# teensyShield4.net
KiCad netlist of a schematic drawn in EAGLE
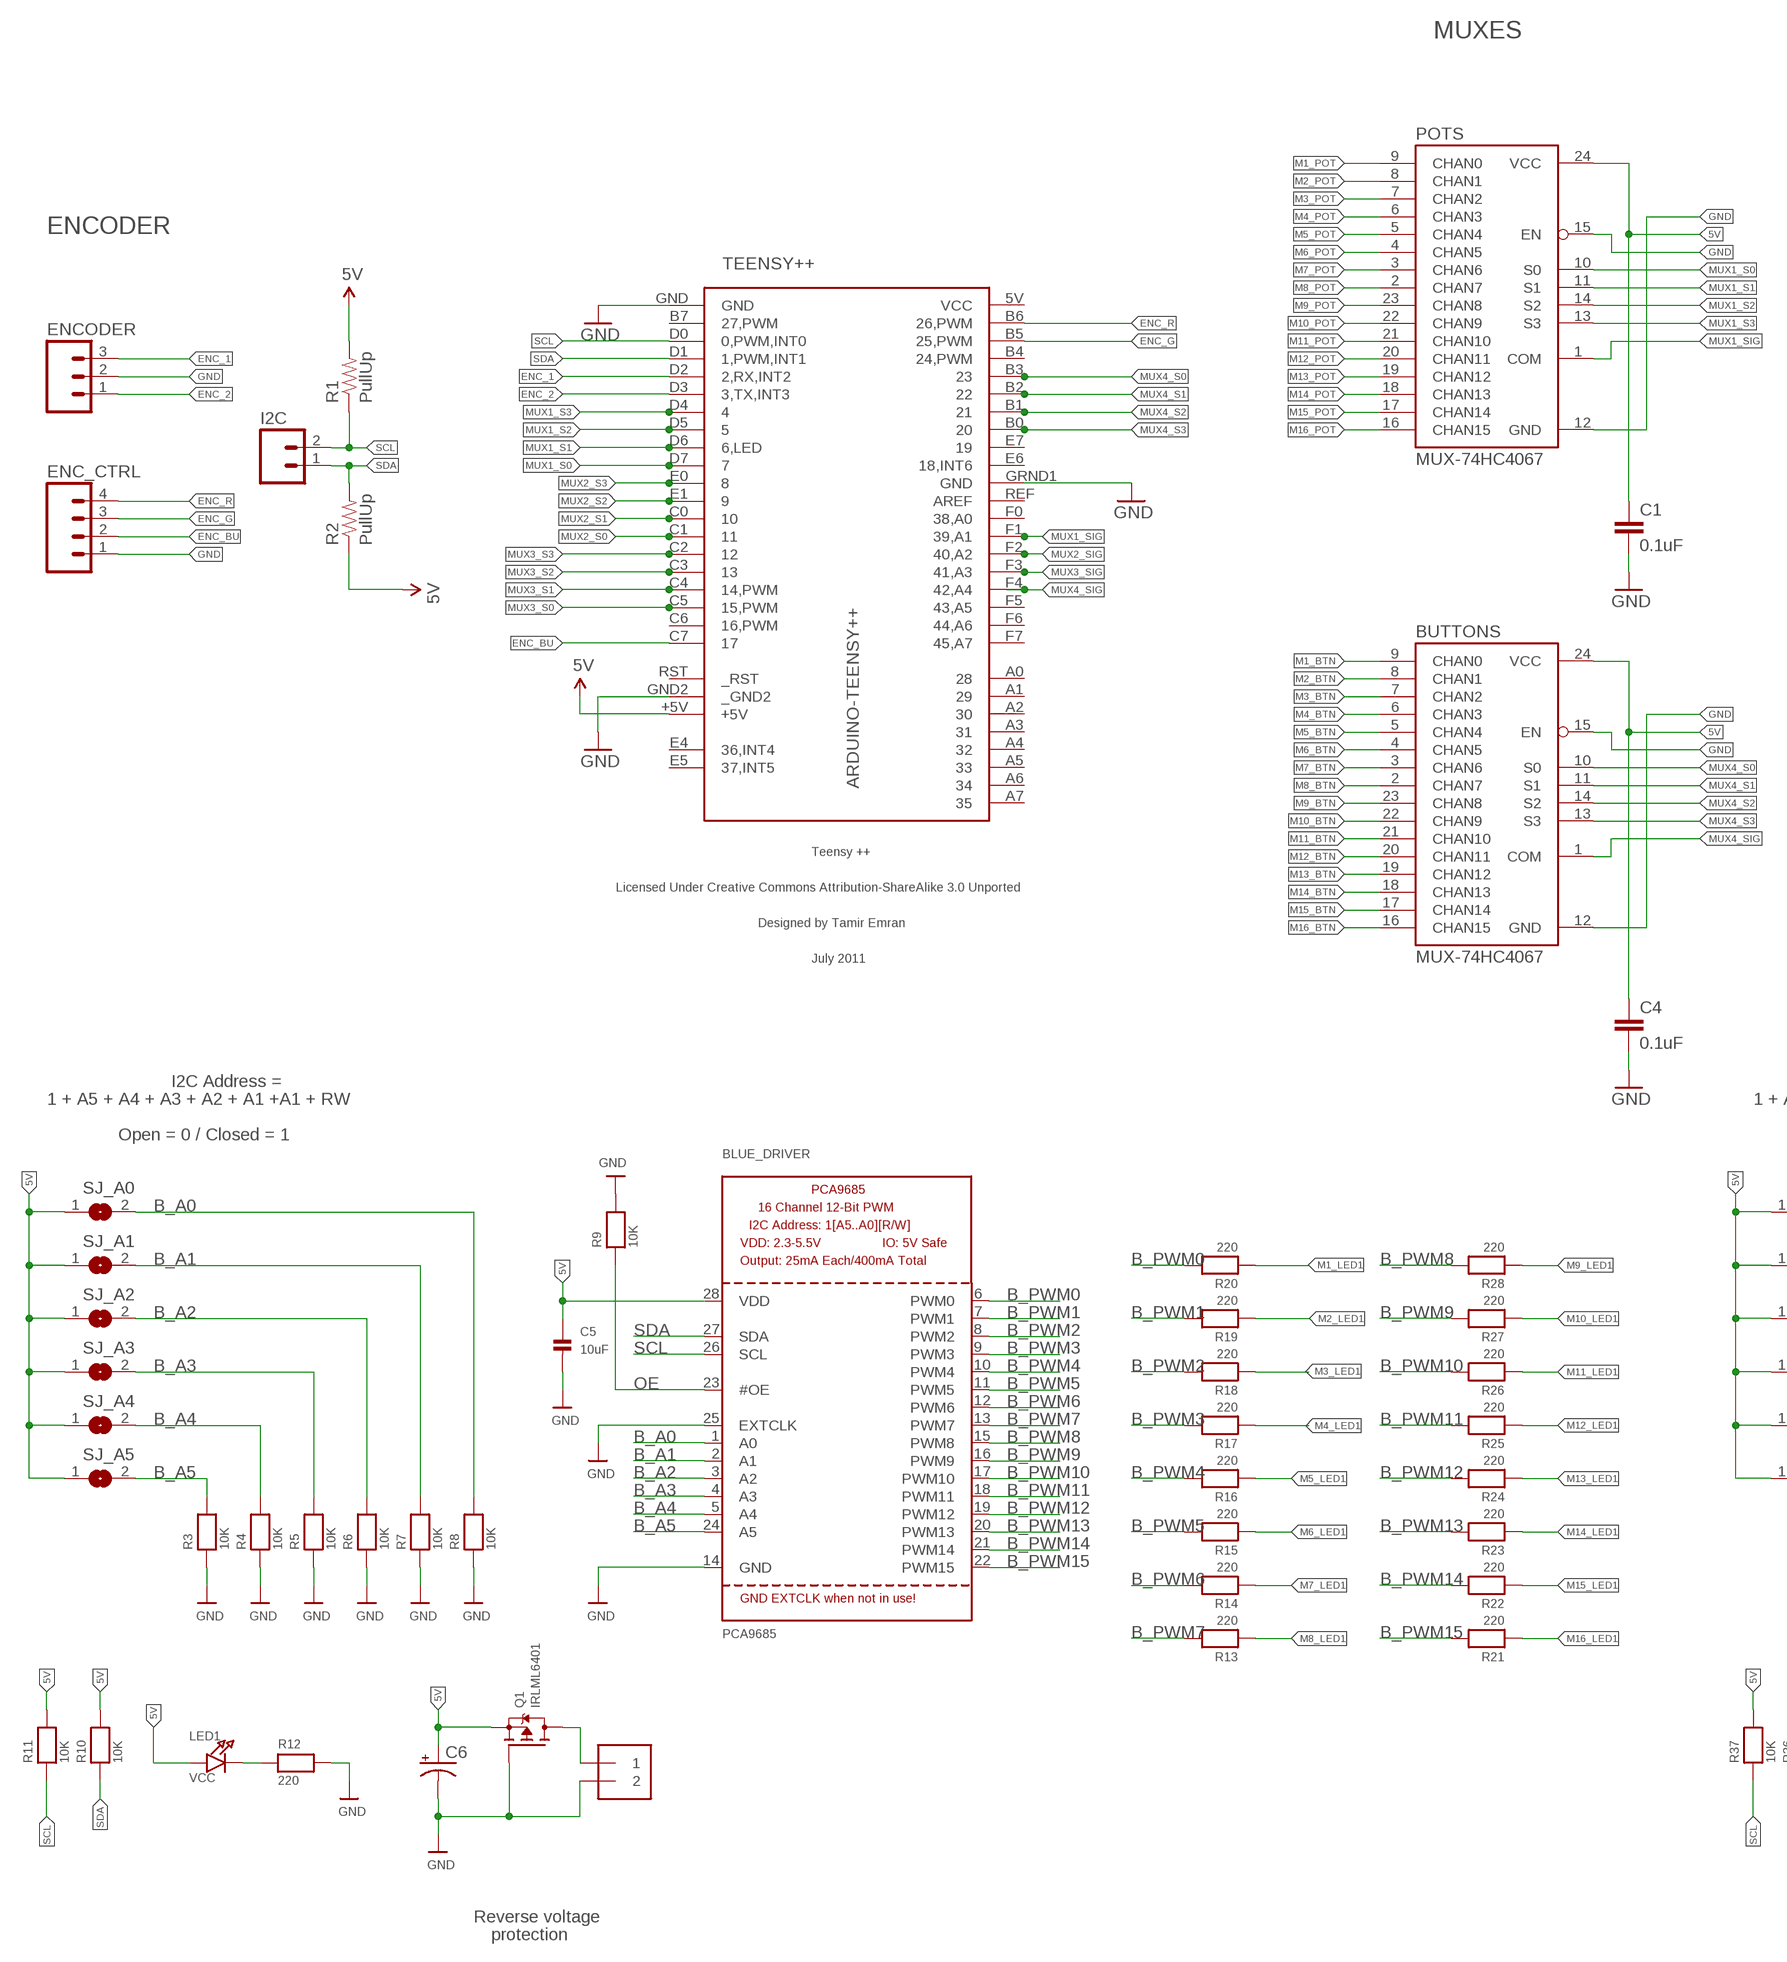
[diagram p0: schematic, sheet 1, part 1 of 2]
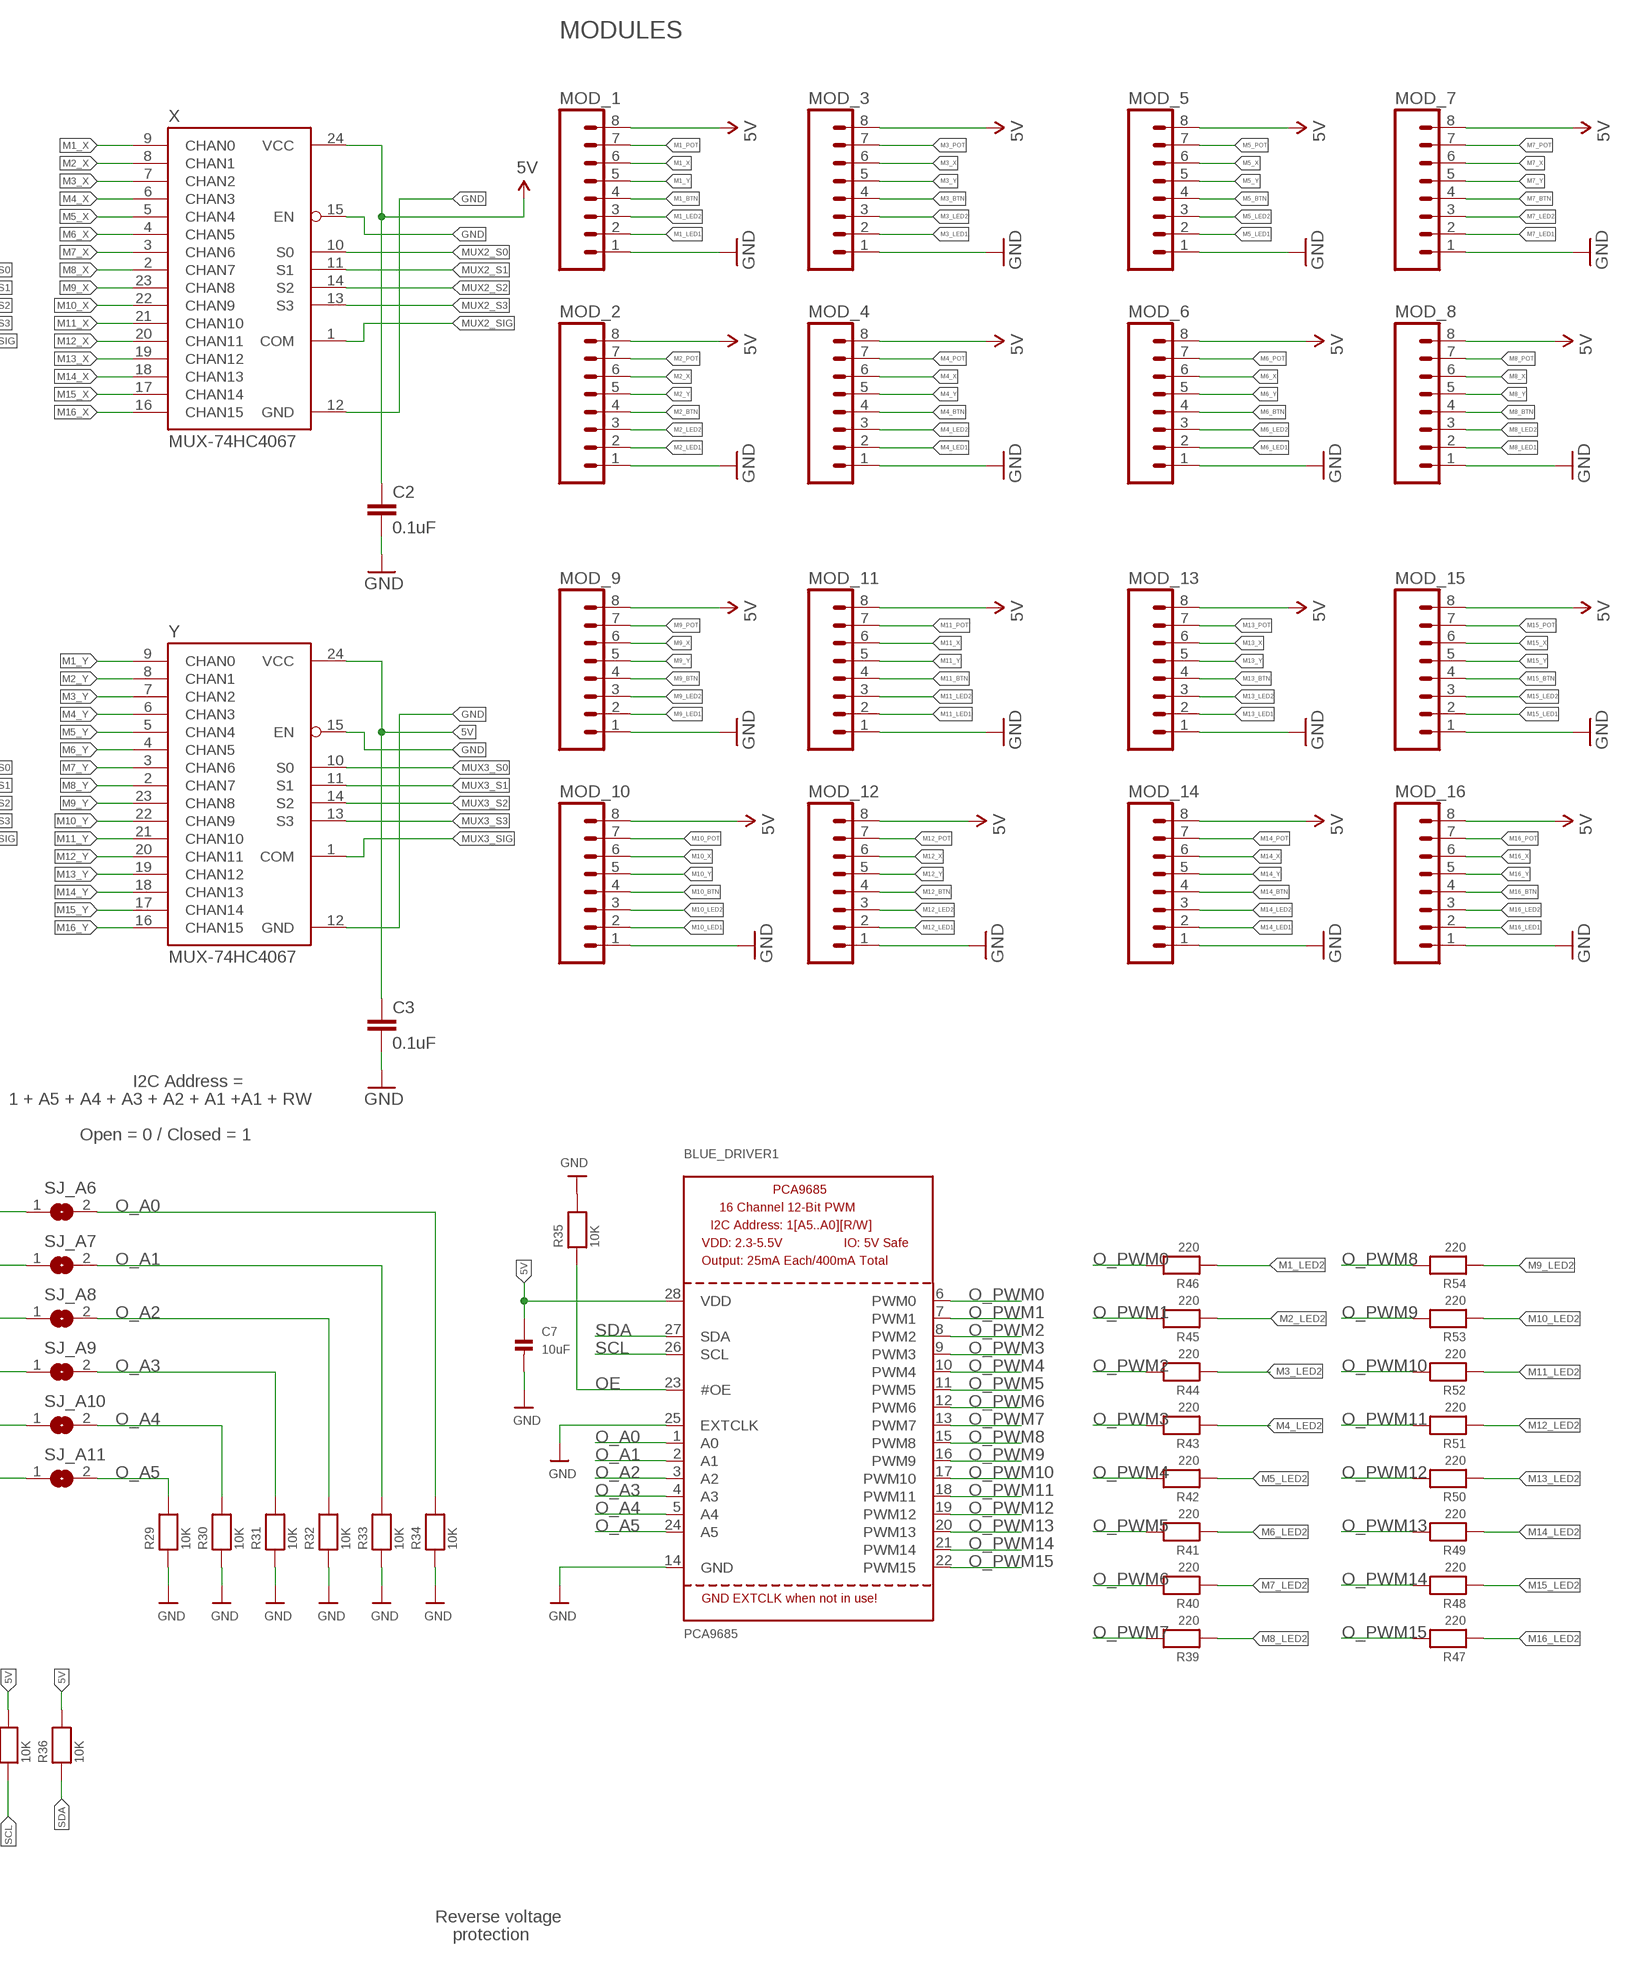
[diagram p1: schematic, sheet 1, part 2 of 2]

(export (version "E")
  (design (tool "Eeschema 10.0.6"))
  (components
    (comp (ref "BLUE_DRIVER")
      (value "PCA9685")
      (footprint "eagle-import:TSSOP28")
      (libsource (lib "eagle-import") (part "PCA9685"))
    )
    (comp (ref "BLUE_DRIVER1")
      (value "PCA9685")
      (footprint "eagle-import:TSSOP28")
      (libsource (lib "eagle-import") (part "PCA9685"))
    )
    (comp (ref "BUTTONS")
      (value "MUX-74HC4067")
      (footprint "eagle-import:SSOP24")
      (libsource (lib "eagle-import") (part "MUX-74HC4067SMD"))
    )
    (comp (ref "C1")
      (value "0.1uF")
      (footprint "eagle-import:0603")
      (libsource (lib "eagle-import") (part "CAP0603"))
    )
    (comp (ref "C2")
      (value "0.1uF")
      (footprint "eagle-import:0603")
      (libsource (lib "eagle-import") (part "CAP0603"))
    )
    (comp (ref "C3")
      (value "0.1uF")
      (footprint "eagle-import:0603")
      (libsource (lib "eagle-import") (part "CAP0603"))
    )
    (comp (ref "C4")
      (value "0.1uF")
      (footprint "eagle-import:0603")
      (libsource (lib "eagle-import") (part "CAP0603"))
    )
    (comp (ref "C5")
      (value "10uF")
      (footprint "eagle-import:0805")
      (libsource (lib "eagle-import") (part "CAP_CERAMIC0805"))
    )
    (comp (ref "C6")
      (value "CPOL-USE3.5-8")
      (footprint "eagle-import:E3,5-8")
      (libsource (lib "eagle-import") (part "CPOL-USE3.5-8"))
    )
    (comp (ref "C7")
      (value "10uF")
      (footprint "eagle-import:0805")
      (libsource (lib "eagle-import") (part "CAP_CERAMIC0805"))
    )
    (comp (ref "ENCODER")
      (value "M031X03_NO_SILK")
      (footprint "eagle-import:1X03_NO_SILK")
      (libsource (lib "eagle-import") (part "M031X03_NO_SILK"))
    )
    (comp (ref "ENC_CTRL")
      (value "M041X04_NO_SILK")
      (footprint "eagle-import:1X04_NO_SILK")
      (libsource (lib "eagle-import") (part "M041X04_NO_SILK"))
    )
    (comp (ref "I2C")
      (value "M02LOCK")
      (footprint "eagle-import:1X02_LOCK")
      (libsource (lib "eagle-import") (part "M02LOCK"))
    )
    (comp (ref "J1")
      (value "TERMBLOCK_1X2-3.5MM")
      (footprint "eagle-import:1X2-3.5MM")
      (libsource (lib "eagle-import") (part "TERMBLOCK_1X2-3.5MM"))
    )
    (comp (ref "LED1")
      (value "VCC")
      (footprint "eagle-import:CHIPLED_0805")
      (libsource (lib "eagle-import") (part "LED0805"))
    )
    (comp (ref "MOD_1")
      (value "M08")
      (footprint "eagle-import:1X08_ROUND")
      (libsource (lib "eagle-import") (part "M08"))
    )
    (comp (ref "MOD_2")
      (value "M08")
      (footprint "eagle-import:1X08_ROUND")
      (libsource (lib "eagle-import") (part "M08"))
    )
    (comp (ref "MOD_3")
      (value "M08")
      (footprint "eagle-import:1X08_ROUND")
      (libsource (lib "eagle-import") (part "M08"))
    )
    (comp (ref "MOD_4")
      (value "M08")
      (footprint "eagle-import:1X08_ROUND")
      (libsource (lib "eagle-import") (part "M08"))
    )
    (comp (ref "MOD_5")
      (value "M08")
      (footprint "eagle-import:1X08_ROUND")
      (libsource (lib "eagle-import") (part "M08"))
    )
    (comp (ref "MOD_6")
      (value "M08")
      (footprint "eagle-import:1X08_ROUND")
      (libsource (lib "eagle-import") (part "M08"))
    )
    (comp (ref "MOD_7")
      (value "M08")
      (footprint "eagle-import:1X08_ROUND")
      (libsource (lib "eagle-import") (part "M08"))
    )
    (comp (ref "MOD_8")
      (value "M08")
      (footprint "eagle-import:1X08_ROUND")
      (libsource (lib "eagle-import") (part "M08"))
    )
    (comp (ref "MOD_9")
      (value "M08")
      (footprint "eagle-import:1X08_ROUND")
      (libsource (lib "eagle-import") (part "M08"))
    )
    (comp (ref "MOD_10")
      (value "M08")
      (footprint "eagle-import:1X08_ROUND")
      (libsource (lib "eagle-import") (part "M08"))
    )
    (comp (ref "MOD_11")
      (value "M08")
      (footprint "eagle-import:1X08_ROUND")
      (libsource (lib "eagle-import") (part "M08"))
    )
    (comp (ref "MOD_12")
      (value "M08")
      (footprint "eagle-import:1X08_ROUND")
      (libsource (lib "eagle-import") (part "M08"))
    )
    (comp (ref "MOD_13")
      (value "M08")
      (footprint "eagle-import:1X08_ROUND")
      (libsource (lib "eagle-import") (part "M08"))
    )
    (comp (ref "MOD_14")
      (value "M08")
      (footprint "eagle-import:1X08_ROUND")
      (libsource (lib "eagle-import") (part "M08"))
    )
    (comp (ref "MOD_15")
      (value "M08")
      (footprint "eagle-import:1X08_ROUND")
      (libsource (lib "eagle-import") (part "M08"))
    )
    (comp (ref "MOD_16")
      (value "M08")
      (footprint "eagle-import:1X08_ROUND")
      (libsource (lib "eagle-import") (part "M08"))
    )
    (comp (ref "POTS")
      (value "MUX-74HC4067")
      (footprint "eagle-import:SSOP24")
      (libsource (lib "eagle-import") (part "MUX-74HC4067SMD"))
    )
    (comp (ref "Q1")
      (value "IRLML6401")
      (footprint "eagle-import:SOT23-WIDE")
      (libsource (lib "eagle-import") (part "MOSFET-PWIDE"))
    )
    (comp (ref "R1")
      (value "PullUp")
      (footprint "eagle-import:AXIAL-0.3")
      (libsource (lib "eagle-import") (part "10KOHM-1/4W5%(PTH)"))
    )
    (comp (ref "R2")
      (value "PullUp")
      (footprint "eagle-import:AXIAL-0.3")
      (libsource (lib "eagle-import") (part "10KOHM-1/4W5%(PTH)"))
    )
    (comp (ref "R3")
      (value "10K")
      (footprint "eagle-import:0805")
      (libsource (lib "eagle-import") (part "RESISTOR0805"))
    )
    (comp (ref "R4")
      (value "10K")
      (footprint "eagle-import:0805")
      (libsource (lib "eagle-import") (part "RESISTOR0805"))
    )
    (comp (ref "R5")
      (value "10K")
      (footprint "eagle-import:0805")
      (libsource (lib "eagle-import") (part "RESISTOR0805"))
    )
    (comp (ref "R6")
      (value "10K")
      (footprint "eagle-import:0805")
      (libsource (lib "eagle-import") (part "RESISTOR0805"))
    )
    (comp (ref "R7")
      (value "10K")
      (footprint "eagle-import:0805")
      (libsource (lib "eagle-import") (part "RESISTOR0805"))
    )
    (comp (ref "R8")
      (value "10K")
      (footprint "eagle-import:0805")
      (libsource (lib "eagle-import") (part "RESISTOR0805"))
    )
    (comp (ref "R9")
      (value "10K")
      (footprint "eagle-import:0805")
      (libsource (lib "eagle-import") (part "RESISTOR0805"))
    )
    (comp (ref "R10")
      (value "10K")
      (footprint "eagle-import:0805")
      (libsource (lib "eagle-import") (part "RESISTOR0805"))
    )
    (comp (ref "R11")
      (value "10K")
      (footprint "eagle-import:0805")
      (libsource (lib "eagle-import") (part "RESISTOR0805"))
    )
    (comp (ref "R12")
      (value "220")
      (footprint "eagle-import:0805")
      (libsource (lib "eagle-import") (part "RESISTOR0805"))
    )
    (comp (ref "R13")
      (value "220")
      (footprint "eagle-import:0805")
      (libsource (lib "eagle-import") (part "RESISTOR0805"))
    )
    (comp (ref "R14")
      (value "220")
      (footprint "eagle-import:0805")
      (libsource (lib "eagle-import") (part "RESISTOR0805"))
    )
    (comp (ref "R15")
      (value "220")
      (footprint "eagle-import:0805")
      (libsource (lib "eagle-import") (part "RESISTOR0805"))
    )
    (comp (ref "R16")
      (value "220")
      (footprint "eagle-import:0805")
      (libsource (lib "eagle-import") (part "RESISTOR0805"))
    )
    (comp (ref "R17")
      (value "220")
      (footprint "eagle-import:0805")
      (libsource (lib "eagle-import") (part "RESISTOR0805"))
    )
    (comp (ref "R18")
      (value "220")
      (footprint "eagle-import:0805")
      (libsource (lib "eagle-import") (part "RESISTOR0805"))
    )
    (comp (ref "R19")
      (value "220")
      (footprint "eagle-import:0805")
      (libsource (lib "eagle-import") (part "RESISTOR0805"))
    )
    (comp (ref "R20")
      (value "220")
      (footprint "eagle-import:0805")
      (libsource (lib "eagle-import") (part "RESISTOR0805"))
    )
    (comp (ref "R21")
      (value "220")
      (footprint "eagle-import:0805")
      (libsource (lib "eagle-import") (part "RESISTOR0805"))
    )
    (comp (ref "R22")
      (value "220")
      (footprint "eagle-import:0805")
      (libsource (lib "eagle-import") (part "RESISTOR0805"))
    )
    (comp (ref "R23")
      (value "220")
      (footprint "eagle-import:0805")
      (libsource (lib "eagle-import") (part "RESISTOR0805"))
    )
    (comp (ref "R24")
      (value "220")
      (footprint "eagle-import:0805")
      (libsource (lib "eagle-import") (part "RESISTOR0805"))
    )
    (comp (ref "R25")
      (value "220")
      (footprint "eagle-import:0805")
      (libsource (lib "eagle-import") (part "RESISTOR0805"))
    )
    (comp (ref "R26")
      (value "220")
      (footprint "eagle-import:0805")
      (libsource (lib "eagle-import") (part "RESISTOR0805"))
    )
    (comp (ref "R27")
      (value "220")
      (footprint "eagle-import:0805")
      (libsource (lib "eagle-import") (part "RESISTOR0805"))
    )
    (comp (ref "R28")
      (value "220")
      (footprint "eagle-import:0805")
      (libsource (lib "eagle-import") (part "RESISTOR0805"))
    )
    (comp (ref "R29")
      (value "10K")
      (footprint "eagle-import:0805")
      (libsource (lib "eagle-import") (part "RESISTOR0805"))
    )
    (comp (ref "R30")
      (value "10K")
      (footprint "eagle-import:0805")
      (libsource (lib "eagle-import") (part "RESISTOR0805"))
    )
    (comp (ref "R31")
      (value "10K")
      (footprint "eagle-import:0805")
      (libsource (lib "eagle-import") (part "RESISTOR0805"))
    )
    (comp (ref "R32")
      (value "10K")
      (footprint "eagle-import:0805")
      (libsource (lib "eagle-import") (part "RESISTOR0805"))
    )
    (comp (ref "R33")
      (value "10K")
      (footprint "eagle-import:0805")
      (libsource (lib "eagle-import") (part "RESISTOR0805"))
    )
    (comp (ref "R34")
      (value "10K")
      (footprint "eagle-import:0805")
      (libsource (lib "eagle-import") (part "RESISTOR0805"))
    )
    (comp (ref "R35")
      (value "10K")
      (footprint "eagle-import:0805")
      (libsource (lib "eagle-import") (part "RESISTOR0805"))
    )
    (comp (ref "R36")
      (value "10K")
      (footprint "eagle-import:0805")
      (libsource (lib "eagle-import") (part "RESISTOR0805"))
    )
    (comp (ref "R37")
      (value "10K")
      (footprint "eagle-import:0805")
      (libsource (lib "eagle-import") (part "RESISTOR0805"))
    )
    (comp (ref "R39")
      (value "220")
      (footprint "eagle-import:0805")
      (libsource (lib "eagle-import") (part "RESISTOR0805"))
    )
    (comp (ref "R40")
      (value "220")
      (footprint "eagle-import:0805")
      (libsource (lib "eagle-import") (part "RESISTOR0805"))
    )
    (comp (ref "R41")
      (value "220")
      (footprint "eagle-import:0805")
      (libsource (lib "eagle-import") (part "RESISTOR0805"))
    )
    (comp (ref "R42")
      (value "220")
      (footprint "eagle-import:0805")
      (libsource (lib "eagle-import") (part "RESISTOR0805"))
    )
    (comp (ref "R43")
      (value "220")
      (footprint "eagle-import:0805")
      (libsource (lib "eagle-import") (part "RESISTOR0805"))
    )
    (comp (ref "R44")
      (value "220")
      (footprint "eagle-import:0805")
      (libsource (lib "eagle-import") (part "RESISTOR0805"))
    )
    (comp (ref "R45")
      (value "220")
      (footprint "eagle-import:0805")
      (libsource (lib "eagle-import") (part "RESISTOR0805"))
    )
    (comp (ref "R46")
      (value "220")
      (footprint "eagle-import:0805")
      (libsource (lib "eagle-import") (part "RESISTOR0805"))
    )
    (comp (ref "R47")
      (value "220")
      (footprint "eagle-import:0805")
      (libsource (lib "eagle-import") (part "RESISTOR0805"))
    )
    (comp (ref "R48")
      (value "220")
      (footprint "eagle-import:0805")
      (libsource (lib "eagle-import") (part "RESISTOR0805"))
    )
    (comp (ref "R49")
      (value "220")
      (footprint "eagle-import:0805")
      (libsource (lib "eagle-import") (part "RESISTOR0805"))
    )
    (comp (ref "R50")
      (value "220")
      (footprint "eagle-import:0805")
      (libsource (lib "eagle-import") (part "RESISTOR0805"))
    )
    (comp (ref "R51")
      (value "220")
      (footprint "eagle-import:0805")
      (libsource (lib "eagle-import") (part "RESISTOR0805"))
    )
    (comp (ref "R52")
      (value "220")
      (footprint "eagle-import:0805")
      (libsource (lib "eagle-import") (part "RESISTOR0805"))
    )
    (comp (ref "R53")
      (value "220")
      (footprint "eagle-import:0805")
      (libsource (lib "eagle-import") (part "RESISTOR0805"))
    )
    (comp (ref "R54")
      (value "220")
      (footprint "eagle-import:0805")
      (libsource (lib "eagle-import") (part "RESISTOR0805"))
    )
    (comp (ref "SJ_A0")
      (value "SOLDERJUMPERREFLOW_NOPASTE")
      (footprint "eagle-import:SOLDERJUMPER_REFLOW_NOPASTE")
      (libsource (lib "eagle-import") (part "SOLDERJUMPERREFLOW_NOPASTE"))
    )
    (comp (ref "SJ_A1")
      (value "SOLDERJUMPERREFLOW_NOPASTE")
      (footprint "eagle-import:SOLDERJUMPER_REFLOW_NOPASTE")
      (libsource (lib "eagle-import") (part "SOLDERJUMPERREFLOW_NOPASTE"))
    )
    (comp (ref "SJ_A2")
      (value "SOLDERJUMPERREFLOW_NOPASTE")
      (footprint "eagle-import:SOLDERJUMPER_REFLOW_NOPASTE")
      (libsource (lib "eagle-import") (part "SOLDERJUMPERREFLOW_NOPASTE"))
    )
    (comp (ref "SJ_A3")
      (value "SOLDERJUMPERREFLOW_NOPASTE")
      (footprint "eagle-import:SOLDERJUMPER_REFLOW_NOPASTE")
      (libsource (lib "eagle-import") (part "SOLDERJUMPERREFLOW_NOPASTE"))
    )
    (comp (ref "SJ_A4")
      (value "SOLDERJUMPERREFLOW_NOPASTE")
      (footprint "eagle-import:SOLDERJUMPER_REFLOW_NOPASTE")
      (libsource (lib "eagle-import") (part "SOLDERJUMPERREFLOW_NOPASTE"))
    )
    (comp (ref "SJ_A5")
      (value "SOLDERJUMPERREFLOW_NOPASTE")
      (footprint "eagle-import:SOLDERJUMPER_REFLOW_NOPASTE")
      (libsource (lib "eagle-import") (part "SOLDERJUMPERREFLOW_NOPASTE"))
    )
    (comp (ref "SJ_A6")
      (value "SOLDERJUMPERREFLOW_NOPASTE")
      (footprint "eagle-import:SOLDERJUMPER_REFLOW_NOPASTE")
      (libsource (lib "eagle-import") (part "SOLDERJUMPERREFLOW_NOPASTE"))
    )
    (comp (ref "SJ_A7")
      (value "SOLDERJUMPERREFLOW_NOPASTE")
      (footprint "eagle-import:SOLDERJUMPER_REFLOW_NOPASTE")
      (libsource (lib "eagle-import") (part "SOLDERJUMPERREFLOW_NOPASTE"))
    )
    (comp (ref "SJ_A8")
      (value "SOLDERJUMPERREFLOW_NOPASTE")
      (footprint "eagle-import:SOLDERJUMPER_REFLOW_NOPASTE")
      (libsource (lib "eagle-import") (part "SOLDERJUMPERREFLOW_NOPASTE"))
    )
    (comp (ref "SJ_A9")
      (value "SOLDERJUMPERREFLOW_NOPASTE")
      (footprint "eagle-import:SOLDERJUMPER_REFLOW_NOPASTE")
      (libsource (lib "eagle-import") (part "SOLDERJUMPERREFLOW_NOPASTE"))
    )
    (comp (ref "SJ_A10")
      (value "SOLDERJUMPERREFLOW_NOPASTE")
      (footprint "eagle-import:SOLDERJUMPER_REFLOW_NOPASTE")
      (libsource (lib "eagle-import") (part "SOLDERJUMPERREFLOW_NOPASTE"))
    )
    (comp (ref "SJ_A11")
      (value "SOLDERJUMPERREFLOW_NOPASTE")
      (footprint "eagle-import:SOLDERJUMPER_REFLOW_NOPASTE")
      (libsource (lib "eagle-import") (part "SOLDERJUMPERREFLOW_NOPASTE"))
    )
    (comp (ref "TEENSY++")
      (value "ARDUINO-TEENSY++")
      (footprint "eagle-import:TEENSY++")
      (libsource (lib "eagle-import") (part "ARDUINO-TEENSY++"))
    )
    (comp (ref "X")
      (value "MUX-74HC4067")
      (footprint "eagle-import:SSOP24")
      (libsource (lib "eagle-import") (part "MUX-74HC4067SMD"))
    )
    (comp (ref "Y")
      (value "MUX-74HC4067")
      (footprint "eagle-import:SSOP24")
      (libsource (lib "eagle-import") (part "MUX-74HC4067SMD"))
    )
  )
  (nets
    (net (code "1") (name "/B_A0") (class "Default")
      (node (ref "BLUE_DRIVER") (pin "1") (pinfunction "A0_1") (pintype "bidirectional"))
      (node (ref "R8") (pin "2") (pinfunction "2_2") (pintype "passive"))
      (node (ref "SJ_A0") (pin "2") (pinfunction "2_2") (pintype "passive"))
    )
    (net (code "2") (name "/B_A1") (class "Default")
      (node (ref "BLUE_DRIVER") (pin "2") (pinfunction "A1_2") (pintype "bidirectional"))
      (node (ref "R7") (pin "2") (pinfunction "2_2") (pintype "passive"))
      (node (ref "SJ_A1") (pin "2") (pinfunction "2_2") (pintype "passive"))
    )
    (net (code "3") (name "/B_A2") (class "Default")
      (node (ref "BLUE_DRIVER") (pin "3") (pinfunction "A2_3") (pintype "bidirectional"))
      (node (ref "R6") (pin "2") (pinfunction "2_2") (pintype "passive"))
      (node (ref "SJ_A2") (pin "2") (pinfunction "2_2") (pintype "passive"))
    )
    (net (code "4") (name "/B_A3") (class "Default")
      (node (ref "BLUE_DRIVER") (pin "4") (pinfunction "A3_4") (pintype "bidirectional"))
      (node (ref "R5") (pin "2") (pinfunction "2_2") (pintype "passive"))
      (node (ref "SJ_A3") (pin "2") (pinfunction "2_2") (pintype "passive"))
    )
    (net (code "5") (name "/B_A4") (class "Default")
      (node (ref "BLUE_DRIVER") (pin "5") (pinfunction "A4_5") (pintype "bidirectional"))
      (node (ref "R4") (pin "2") (pinfunction "2_2") (pintype "passive"))
      (node (ref "SJ_A4") (pin "2") (pinfunction "2_2") (pintype "passive"))
    )
    (net (code "6") (name "/B_A5") (class "Default")
      (node (ref "BLUE_DRIVER") (pin "24") (pinfunction "A5_24") (pintype "bidirectional"))
      (node (ref "R3") (pin "2") (pinfunction "2_2") (pintype "passive"))
      (node (ref "SJ_A5") (pin "2") (pinfunction "2_2") (pintype "passive"))
    )
    (net (code "7") (name "/B_PWM0") (class "Default")
      (node (ref "BLUE_DRIVER") (pin "6") (pinfunction "PWM0_6") (pintype "output"))
      (node (ref "R20") (pin "2") (pinfunction "2_2") (pintype "passive"))
    )
    (net (code "8") (name "/B_PWM1") (class "Default")
      (node (ref "BLUE_DRIVER") (pin "7") (pinfunction "PWM1_7") (pintype "output"))
      (node (ref "R19") (pin "2") (pinfunction "2_2") (pintype "passive"))
    )
    (net (code "9") (name "/B_PWM2") (class "Default")
      (node (ref "BLUE_DRIVER") (pin "8") (pinfunction "PWM2_8") (pintype "output"))
      (node (ref "R18") (pin "2") (pinfunction "2_2") (pintype "passive"))
    )
    (net (code "10") (name "/B_PWM3") (class "Default")
      (node (ref "BLUE_DRIVER") (pin "9") (pinfunction "PWM3_9") (pintype "output"))
      (node (ref "R17") (pin "2") (pinfunction "2_2") (pintype "passive"))
    )
    (net (code "11") (name "/B_PWM4") (class "Default")
      (node (ref "BLUE_DRIVER") (pin "10") (pinfunction "PWM4_10") (pintype "output"))
      (node (ref "R16") (pin "2") (pinfunction "2_2") (pintype "passive"))
    )
    (net (code "12") (name "/B_PWM5") (class "Default")
      (node (ref "BLUE_DRIVER") (pin "11") (pinfunction "PWM5_11") (pintype "output"))
      (node (ref "R15") (pin "2") (pinfunction "2_2") (pintype "passive"))
    )
    (net (code "13") (name "/B_PWM6") (class "Default")
      (node (ref "BLUE_DRIVER") (pin "12") (pinfunction "PWM6_12") (pintype "output"))
      (node (ref "R14") (pin "2") (pinfunction "2_2") (pintype "passive"))
    )
    (net (code "14") (name "/B_PWM7") (class "Default")
      (node (ref "BLUE_DRIVER") (pin "13") (pinfunction "PWM7_13") (pintype "output"))
      (node (ref "R13") (pin "2") (pinfunction "2_2") (pintype "passive"))
    )
    (net (code "15") (name "/B_PWM8") (class "Default")
      (node (ref "BLUE_DRIVER") (pin "15") (pinfunction "PWM8_15") (pintype "output"))
      (node (ref "R28") (pin "2") (pinfunction "2_2") (pintype "passive"))
    )
    (net (code "16") (name "/B_PWM9") (class "Default")
      (node (ref "BLUE_DRIVER") (pin "16") (pinfunction "PWM9_16") (pintype "output"))
      (node (ref "R27") (pin "2") (pinfunction "2_2") (pintype "passive"))
    )
    (net (code "17") (name "/B_PWM10") (class "Default")
      (node (ref "BLUE_DRIVER") (pin "17") (pinfunction "PWM10_17") (pintype "output"))
      (node (ref "R26") (pin "2") (pinfunction "2_2") (pintype "passive"))
    )
    (net (code "18") (name "/B_PWM11") (class "Default")
      (node (ref "BLUE_DRIVER") (pin "18") (pinfunction "PWM11_18") (pintype "output"))
      (node (ref "R25") (pin "2") (pinfunction "2_2") (pintype "passive"))
    )
    (net (code "19") (name "/B_PWM12") (class "Default")
      (node (ref "BLUE_DRIVER") (pin "19") (pinfunction "PWM12_19") (pintype "output"))
      (node (ref "R24") (pin "2") (pinfunction "2_2") (pintype "passive"))
    )
    (net (code "20") (name "/B_PWM13") (class "Default")
      (node (ref "BLUE_DRIVER") (pin "20") (pinfunction "PWM13_20") (pintype "output"))
      (node (ref "R23") (pin "2") (pinfunction "2_2") (pintype "passive"))
    )
    (net (code "21") (name "/B_PWM14") (class "Default")
      (node (ref "BLUE_DRIVER") (pin "21") (pinfunction "PWM14_21") (pintype "output"))
      (node (ref "R22") (pin "2") (pinfunction "2_2") (pintype "passive"))
    )
    (net (code "22") (name "/B_PWM15") (class "Default")
      (node (ref "BLUE_DRIVER") (pin "22") (pinfunction "PWM15_22") (pintype "output"))
      (node (ref "R21") (pin "2") (pinfunction "2_2") (pintype "passive"))
    )
    (net (code "23") (name "/OE") (class "Default")
      (node (ref "BLUE_DRIVER") (pin "23") (pinfunction "#OE_23") (pintype "input"))
      (node (ref "BLUE_DRIVER1") (pin "23") (pinfunction "#OE_23") (pintype "input"))
      (node (ref "R35") (pin "1") (pinfunction "1_1") (pintype "passive"))
      (node (ref "R9") (pin "1") (pinfunction "1_1") (pintype "passive"))
    )
    (net (code "24") (name "/O_A0") (class "Default")
      (node (ref "BLUE_DRIVER1") (pin "1") (pinfunction "A0_1") (pintype "bidirectional"))
      (node (ref "R34") (pin "2") (pinfunction "2_2") (pintype "passive"))
      (node (ref "SJ_A6") (pin "2") (pinfunction "2_2") (pintype "passive"))
    )
    (net (code "25") (name "/O_A1") (class "Default")
      (node (ref "BLUE_DRIVER1") (pin "2") (pinfunction "A1_2") (pintype "bidirectional"))
      (node (ref "R33") (pin "2") (pinfunction "2_2") (pintype "passive"))
      (node (ref "SJ_A7") (pin "2") (pinfunction "2_2") (pintype "passive"))
    )
    (net (code "26") (name "/O_A2") (class "Default")
      (node (ref "BLUE_DRIVER1") (pin "3") (pinfunction "A2_3") (pintype "bidirectional"))
      (node (ref "R32") (pin "2") (pinfunction "2_2") (pintype "passive"))
      (node (ref "SJ_A8") (pin "2") (pinfunction "2_2") (pintype "passive"))
    )
    (net (code "27") (name "/O_A3") (class "Default")
      (node (ref "BLUE_DRIVER1") (pin "4") (pinfunction "A3_4") (pintype "bidirectional"))
      (node (ref "R31") (pin "2") (pinfunction "2_2") (pintype "passive"))
      (node (ref "SJ_A9") (pin "2") (pinfunction "2_2") (pintype "passive"))
    )
    (net (code "28") (name "/O_A4") (class "Default")
      (node (ref "BLUE_DRIVER1") (pin "5") (pinfunction "A4_5") (pintype "bidirectional"))
      (node (ref "R30") (pin "2") (pinfunction "2_2") (pintype "passive"))
      (node (ref "SJ_A10") (pin "2") (pinfunction "2_2") (pintype "passive"))
    )
    (net (code "29") (name "/O_A5") (class "Default")
      (node (ref "BLUE_DRIVER1") (pin "24") (pinfunction "A5_24") (pintype "bidirectional"))
      (node (ref "R29") (pin "2") (pinfunction "2_2") (pintype "passive"))
      (node (ref "SJ_A11") (pin "2") (pinfunction "2_2") (pintype "passive"))
    )
    (net (code "30") (name "/O_PWM0") (class "Default")
      (node (ref "BLUE_DRIVER1") (pin "6") (pinfunction "PWM0_6") (pintype "output"))
      (node (ref "R46") (pin "2") (pinfunction "2_2") (pintype "passive"))
    )
    (net (code "31") (name "/O_PWM1") (class "Default")
      (node (ref "BLUE_DRIVER1") (pin "7") (pinfunction "PWM1_7") (pintype "output"))
      (node (ref "R45") (pin "2") (pinfunction "2_2") (pintype "passive"))
    )
    (net (code "32") (name "/O_PWM2") (class "Default")
      (node (ref "BLUE_DRIVER1") (pin "8") (pinfunction "PWM2_8") (pintype "output"))
      (node (ref "R44") (pin "2") (pinfunction "2_2") (pintype "passive"))
    )
    (net (code "33") (name "/O_PWM3") (class "Default")
      (node (ref "BLUE_DRIVER1") (pin "9") (pinfunction "PWM3_9") (pintype "output"))
      (node (ref "R43") (pin "2") (pinfunction "2_2") (pintype "passive"))
    )
    (net (code "34") (name "/O_PWM4") (class "Default")
      (node (ref "BLUE_DRIVER1") (pin "10") (pinfunction "PWM4_10") (pintype "output"))
      (node (ref "R42") (pin "2") (pinfunction "2_2") (pintype "passive"))
    )
    (net (code "35") (name "/O_PWM5") (class "Default")
      (node (ref "BLUE_DRIVER1") (pin "11") (pinfunction "PWM5_11") (pintype "output"))
      (node (ref "R41") (pin "2") (pinfunction "2_2") (pintype "passive"))
    )
    (net (code "36") (name "/O_PWM6") (class "Default")
      (node (ref "BLUE_DRIVER1") (pin "12") (pinfunction "PWM6_12") (pintype "output"))
      (node (ref "R40") (pin "2") (pinfunction "2_2") (pintype "passive"))
    )
    (net (code "37") (name "/O_PWM7") (class "Default")
      (node (ref "BLUE_DRIVER1") (pin "13") (pinfunction "PWM7_13") (pintype "output"))
      (node (ref "R39") (pin "2") (pinfunction "2_2") (pintype "passive"))
    )
    (net (code "38") (name "/O_PWM8") (class "Default")
      (node (ref "BLUE_DRIVER1") (pin "15") (pinfunction "PWM8_15") (pintype "output"))
      (node (ref "R54") (pin "2") (pinfunction "2_2") (pintype "passive"))
    )
    (net (code "39") (name "/O_PWM9") (class "Default")
      (node (ref "BLUE_DRIVER1") (pin "16") (pinfunction "PWM9_16") (pintype "output"))
      (node (ref "R53") (pin "2") (pinfunction "2_2") (pintype "passive"))
    )
    (net (code "40") (name "/O_PWM10") (class "Default")
      (node (ref "BLUE_DRIVER1") (pin "17") (pinfunction "PWM10_17") (pintype "output"))
      (node (ref "R52") (pin "2") (pinfunction "2_2") (pintype "passive"))
    )
    (net (code "41") (name "/O_PWM11") (class "Default")
      (node (ref "BLUE_DRIVER1") (pin "18") (pinfunction "PWM11_18") (pintype "output"))
      (node (ref "R51") (pin "2") (pinfunction "2_2") (pintype "passive"))
    )
    (net (code "42") (name "/O_PWM12") (class "Default")
      (node (ref "BLUE_DRIVER1") (pin "19") (pinfunction "PWM12_19") (pintype "output"))
      (node (ref "R50") (pin "2") (pinfunction "2_2") (pintype "passive"))
    )
    (net (code "43") (name "/O_PWM13") (class "Default")
      (node (ref "BLUE_DRIVER1") (pin "20") (pinfunction "PWM13_20") (pintype "output"))
      (node (ref "R49") (pin "2") (pinfunction "2_2") (pintype "passive"))
    )
    (net (code "44") (name "/O_PWM14") (class "Default")
      (node (ref "BLUE_DRIVER1") (pin "21") (pinfunction "PWM14_21") (pintype "output"))
      (node (ref "R48") (pin "2") (pinfunction "2_2") (pintype "passive"))
    )
    (net (code "45") (name "/O_PWM15") (class "Default")
      (node (ref "BLUE_DRIVER1") (pin "22") (pinfunction "PWM15_22") (pintype "output"))
      (node (ref "R47") (pin "2") (pinfunction "2_2") (pintype "passive"))
    )
    (net (code "46") (name "/VCC") (class "Default")
      (node (ref "TEENSY++") (pin "5V") (pinfunction "VCC_5V") (pintype "power_in"))
    )
    (net (code "47") (name "5V") (class "Default")
      (node (ref "BLUE_DRIVER") (pin "28") (pinfunction "VDD_28") (pintype "power_in"))
      (node (ref "BLUE_DRIVER1") (pin "28") (pinfunction "VDD_28") (pintype "power_in"))
      (node (ref "BUTTONS") (pin "24") (pinfunction "VCC_24") (pintype "bidirectional"))
      (node (ref "C1") (pin "1") (pinfunction "1_1") (pintype "passive"))
      (node (ref "C2") (pin "1") (pinfunction "1_1") (pintype "passive"))
      (node (ref "C3") (pin "1") (pinfunction "1_1") (pintype "passive"))
      (node (ref "C4") (pin "1") (pinfunction "1_1") (pintype "passive"))
      (node (ref "C5") (pin "1") (pinfunction "P$1_1") (pintype "passive"))
      (node (ref "C6") (pin "+") (pinfunction "+_+") (pintype "passive"))
      (node (ref "C7") (pin "1") (pinfunction "P$1_1") (pintype "passive"))
      (node (ref "LED1") (pin "A") (pinfunction "A_A") (pintype "passive"))
      (node (ref "MOD_1") (pin "8") (pinfunction "8_8") (pintype "passive"))
      (node (ref "MOD_10") (pin "8") (pinfunction "8_8") (pintype "passive"))
      (node (ref "MOD_11") (pin "8") (pinfunction "8_8") (pintype "passive"))
      (node (ref "MOD_12") (pin "8") (pinfunction "8_8") (pintype "passive"))
      (node (ref "MOD_13") (pin "8") (pinfunction "8_8") (pintype "passive"))
      (node (ref "MOD_14") (pin "8") (pinfunction "8_8") (pintype "passive"))
      (node (ref "MOD_15") (pin "8") (pinfunction "8_8") (pintype "passive"))
      (node (ref "MOD_16") (pin "8") (pinfunction "8_8") (pintype "passive"))
      (node (ref "MOD_2") (pin "8") (pinfunction "8_8") (pintype "passive"))
      (node (ref "MOD_3") (pin "8") (pinfunction "8_8") (pintype "passive"))
      (node (ref "MOD_4") (pin "8") (pinfunction "8_8") (pintype "passive"))
      (node (ref "MOD_5") (pin "8") (pinfunction "8_8") (pintype "passive"))
      (node (ref "MOD_6") (pin "8") (pinfunction "8_8") (pintype "passive"))
      (node (ref "MOD_7") (pin "8") (pinfunction "8_8") (pintype "passive"))
      (node (ref "MOD_8") (pin "8") (pinfunction "8_8") (pintype "passive"))
      (node (ref "MOD_9") (pin "8") (pinfunction "8_8") (pintype "passive"))
      (node (ref "POTS") (pin "24") (pinfunction "VCC_24") (pintype "bidirectional"))
      (node (ref "Q1") (pin "2") (pinfunction "S_2") (pintype "passive"))
      (node (ref "R1") (pin "P$2") (pinfunction "2_P$2") (pintype "passive"))
      (node (ref "R10") (pin "2") (pinfunction "2_2") (pintype "passive"))
      (node (ref "R11") (pin "2") (pinfunction "2_2") (pintype "passive"))
      (node (ref "R2") (pin "P$1") (pinfunction "1_P$1") (pintype "passive"))
      (node (ref "R36") (pin "2") (pinfunction "2_2") (pintype "passive"))
      (node (ref "R37") (pin "2") (pinfunction "2_2") (pintype "passive"))
      (node (ref "SJ_A0") (pin "1") (pinfunction "1_1") (pintype "passive"))
      (node (ref "SJ_A1") (pin "1") (pinfunction "1_1") (pintype "passive"))
      (node (ref "SJ_A10") (pin "1") (pinfunction "1_1") (pintype "passive"))
      (node (ref "SJ_A11") (pin "1") (pinfunction "1_1") (pintype "passive"))
      (node (ref "SJ_A2") (pin "1") (pinfunction "1_1") (pintype "passive"))
      (node (ref "SJ_A3") (pin "1") (pinfunction "1_1") (pintype "passive"))
      (node (ref "SJ_A4") (pin "1") (pinfunction "1_1") (pintype "passive"))
      (node (ref "SJ_A5") (pin "1") (pinfunction "1_1") (pintype "passive"))
      (node (ref "SJ_A6") (pin "1") (pinfunction "1_1") (pintype "passive"))
      (node (ref "SJ_A7") (pin "1") (pinfunction "1_1") (pintype "passive"))
      (node (ref "SJ_A8") (pin "1") (pinfunction "1_1") (pintype "passive"))
      (node (ref "SJ_A9") (pin "1") (pinfunction "1_1") (pintype "passive"))
      (node (ref "TEENSY++") (pin "+5V") (pinfunction "+5V_+5V") (pintype "power_in"))
      (node (ref "X") (pin "24") (pinfunction "VCC_24") (pintype "bidirectional"))
      (node (ref "Y") (pin "24") (pinfunction "VCC_24") (pintype "bidirectional"))
    )
    (net (code "48") (name "ENC_1") (class "Default")
      (node (ref "ENCODER") (pin "3") (pinfunction "3_3") (pintype "passive"))
      (node (ref "TEENSY++") (pin "D2") (pinfunction "2,RX,INT2_D2") (pintype "bidirectional"))
    )
    (net (code "49") (name "ENC_2") (class "Default")
      (node (ref "ENCODER") (pin "1") (pinfunction "1_1") (pintype "passive"))
      (node (ref "TEENSY++") (pin "D3") (pinfunction "3,TX,INT3_D3") (pintype "bidirectional"))
    )
    (net (code "50") (name "ENC_BU") (class "Default")
      (node (ref "ENC_CTRL") (pin "2") (pinfunction "2_2") (pintype "passive"))
      (node (ref "TEENSY++") (pin "C7") (pinfunction "17_C7") (pintype "bidirectional"))
    )
    (net (code "51") (name "ENC_G") (class "Default")
      (node (ref "ENC_CTRL") (pin "3") (pinfunction "3_3") (pintype "passive"))
      (node (ref "TEENSY++") (pin "B5") (pinfunction "25,PWM_B5") (pintype "bidirectional"))
    )
    (net (code "52") (name "ENC_R") (class "Default")
      (node (ref "ENC_CTRL") (pin "4") (pinfunction "4_4") (pintype "passive"))
      (node (ref "TEENSY++") (pin "B6") (pinfunction "26,PWM_B6") (pintype "bidirectional"))
    )
    (net (code "53") (name "GND") (class "Default")
      (node (ref "BLUE_DRIVER") (pin "14") (pinfunction "GND_14") (pintype "power_in"))
      (node (ref "BLUE_DRIVER") (pin "25") (pinfunction "EXTCLK_25") (pintype "input"))
      (node (ref "BLUE_DRIVER1") (pin "14") (pinfunction "GND_14") (pintype "power_in"))
      (node (ref "BLUE_DRIVER1") (pin "25") (pinfunction "EXTCLK_25") (pintype "input"))
      (node (ref "BUTTONS") (pin "12") (pinfunction "GND_12") (pintype "bidirectional"))
      (node (ref "BUTTONS") (pin "15") (pinfunction "EN_15") (pintype "input"))
      (node (ref "C1") (pin "2") (pinfunction "2_2") (pintype "passive"))
      (node (ref "C2") (pin "2") (pinfunction "2_2") (pintype "passive"))
      (node (ref "C3") (pin "2") (pinfunction "2_2") (pintype "passive"))
      (node (ref "C4") (pin "2") (pinfunction "2_2") (pintype "passive"))
      (node (ref "C5") (pin "2") (pinfunction "P$2_2") (pintype "passive"))
      (node (ref "C6") (pin "-") (pinfunction "-_-") (pintype "passive"))
      (node (ref "C7") (pin "2") (pinfunction "P$2_2") (pintype "passive"))
      (node (ref "ENCODER") (pin "2") (pinfunction "2_2") (pintype "passive"))
      (node (ref "ENC_CTRL") (pin "1") (pinfunction "1_1") (pintype "passive"))
      (node (ref "J1") (pin "2") (pinfunction "2_2") (pintype "passive"))
      (node (ref "MOD_1") (pin "1") (pinfunction "1_1") (pintype "passive"))
      (node (ref "MOD_10") (pin "1") (pinfunction "1_1") (pintype "passive"))
      (node (ref "MOD_11") (pin "1") (pinfunction "1_1") (pintype "passive"))
      (node (ref "MOD_12") (pin "1") (pinfunction "1_1") (pintype "passive"))
      (node (ref "MOD_13") (pin "1") (pinfunction "1_1") (pintype "passive"))
      (node (ref "MOD_14") (pin "1") (pinfunction "1_1") (pintype "passive"))
      (node (ref "MOD_15") (pin "1") (pinfunction "1_1") (pintype "passive"))
      (node (ref "MOD_16") (pin "1") (pinfunction "1_1") (pintype "passive"))
      (node (ref "MOD_2") (pin "1") (pinfunction "1_1") (pintype "passive"))
      (node (ref "MOD_3") (pin "1") (pinfunction "1_1") (pintype "passive"))
      (node (ref "MOD_4") (pin "1") (pinfunction "1_1") (pintype "passive"))
      (node (ref "MOD_5") (pin "1") (pinfunction "1_1") (pintype "passive"))
      (node (ref "MOD_6") (pin "1") (pinfunction "1_1") (pintype "passive"))
      (node (ref "MOD_7") (pin "1") (pinfunction "1_1") (pintype "passive"))
      (node (ref "MOD_8") (pin "1") (pinfunction "1_1") (pintype "passive"))
      (node (ref "MOD_9") (pin "1") (pinfunction "1_1") (pintype "passive"))
      (node (ref "POTS") (pin "12") (pinfunction "GND_12") (pintype "bidirectional"))
      (node (ref "POTS") (pin "15") (pinfunction "EN_15") (pintype "input"))
      (node (ref "Q1") (pin "1") (pinfunction "G_1") (pintype "passive"))
      (node (ref "R12") (pin "2") (pinfunction "2_2") (pintype "passive"))
      (node (ref "R29") (pin "1") (pinfunction "1_1") (pintype "passive"))
      (node (ref "R3") (pin "1") (pinfunction "1_1") (pintype "passive"))
      (node (ref "R30") (pin "1") (pinfunction "1_1") (pintype "passive"))
      (node (ref "R31") (pin "1") (pinfunction "1_1") (pintype "passive"))
      (node (ref "R32") (pin "1") (pinfunction "1_1") (pintype "passive"))
      (node (ref "R33") (pin "1") (pinfunction "1_1") (pintype "passive"))
      (node (ref "R34") (pin "1") (pinfunction "1_1") (pintype "passive"))
      (node (ref "R35") (pin "2") (pinfunction "2_2") (pintype "passive"))
      (node (ref "R4") (pin "1") (pinfunction "1_1") (pintype "passive"))
      (node (ref "R5") (pin "1") (pinfunction "1_1") (pintype "passive"))
      (node (ref "R6") (pin "1") (pinfunction "1_1") (pintype "passive"))
      (node (ref "R7") (pin "1") (pinfunction "1_1") (pintype "passive"))
      (node (ref "R8") (pin "1") (pinfunction "1_1") (pintype "passive"))
      (node (ref "R9") (pin "2") (pinfunction "2_2") (pintype "passive"))
      (node (ref "TEENSY++") (pin "GND") (pinfunction "GND_GND") (pintype "power_in"))
      (node (ref "TEENSY++") (pin "GND2") (pinfunction "_GND2_GND2") (pintype "power_in"))
      (node (ref "TEENSY++") (pin "GRND1") (pinfunction "GND_GRND1") (pintype "power_in"))
      (node (ref "X") (pin "12") (pinfunction "GND_12") (pintype "bidirectional"))
      (node (ref "X") (pin "15") (pinfunction "EN_15") (pintype "input"))
      (node (ref "Y") (pin "12") (pinfunction "GND_12") (pintype "bidirectional"))
      (node (ref "Y") (pin "15") (pinfunction "EN_15") (pintype "input"))
    )
    (net (code "54") (name "M1_BTN") (class "Default")
      (node (ref "BUTTONS") (pin "9") (pinfunction "CHAN0_9") (pintype "bidirectional"))
      (node (ref "MOD_1") (pin "4") (pinfunction "4_4") (pintype "passive"))
    )
    (net (code "55") (name "M1_LED1") (class "Default")
      (node (ref "MOD_1") (pin "2") (pinfunction "2_2") (pintype "passive"))
      (node (ref "R20") (pin "1") (pinfunction "1_1") (pintype "passive"))
    )
    (net (code "56") (name "M1_LED2") (class "Default")
      (node (ref "MOD_1") (pin "3") (pinfunction "3_3") (pintype "passive"))
      (node (ref "R46") (pin "1") (pinfunction "1_1") (pintype "passive"))
    )
    (net (code "57") (name "M1_POT") (class "Default")
      (node (ref "MOD_1") (pin "7") (pinfunction "7_7") (pintype "passive"))
      (node (ref "POTS") (pin "9") (pinfunction "CHAN0_9") (pintype "bidirectional"))
    )
    (net (code "58") (name "M1_X") (class "Default")
      (node (ref "MOD_1") (pin "6") (pinfunction "6_6") (pintype "passive"))
      (node (ref "X") (pin "9") (pinfunction "CHAN0_9") (pintype "bidirectional"))
    )
    (net (code "59") (name "M1_Y") (class "Default")
      (node (ref "MOD_1") (pin "5") (pinfunction "5_5") (pintype "passive"))
      (node (ref "Y") (pin "9") (pinfunction "CHAN0_9") (pintype "bidirectional"))
    )
    (net (code "60") (name "M2_BTN") (class "Default")
      (node (ref "BUTTONS") (pin "8") (pinfunction "CHAN1_8") (pintype "bidirectional"))
      (node (ref "MOD_2") (pin "4") (pinfunction "4_4") (pintype "passive"))
    )
    (net (code "61") (name "M2_LED1") (class "Default")
      (node (ref "MOD_2") (pin "2") (pinfunction "2_2") (pintype "passive"))
      (node (ref "R19") (pin "1") (pinfunction "1_1") (pintype "passive"))
    )
    (net (code "62") (name "M2_LED2") (class "Default")
      (node (ref "MOD_2") (pin "3") (pinfunction "3_3") (pintype "passive"))
      (node (ref "R45") (pin "1") (pinfunction "1_1") (pintype "passive"))
    )
    (net (code "63") (name "M2_POT") (class "Default")
      (node (ref "MOD_2") (pin "7") (pinfunction "7_7") (pintype "passive"))
      (node (ref "POTS") (pin "8") (pinfunction "CHAN1_8") (pintype "bidirectional"))
    )
    (net (code "64") (name "M2_X") (class "Default")
      (node (ref "MOD_2") (pin "6") (pinfunction "6_6") (pintype "passive"))
      (node (ref "X") (pin "8") (pinfunction "CHAN1_8") (pintype "bidirectional"))
    )
    (net (code "65") (name "M2_Y") (class "Default")
      (node (ref "MOD_2") (pin "5") (pinfunction "5_5") (pintype "passive"))
      (node (ref "Y") (pin "8") (pinfunction "CHAN1_8") (pintype "bidirectional"))
    )
    (net (code "66") (name "M3_BTN") (class "Default")
      (node (ref "BUTTONS") (pin "7") (pinfunction "CHAN2_7") (pintype "bidirectional"))
      (node (ref "MOD_3") (pin "4") (pinfunction "4_4") (pintype "passive"))
    )
    (net (code "67") (name "M3_LED1") (class "Default")
      (node (ref "MOD_3") (pin "2") (pinfunction "2_2") (pintype "passive"))
      (node (ref "R18") (pin "1") (pinfunction "1_1") (pintype "passive"))
    )
    (net (code "68") (name "M3_LED2") (class "Default")
      (node (ref "MOD_3") (pin "3") (pinfunction "3_3") (pintype "passive"))
      (node (ref "R44") (pin "1") (pinfunction "1_1") (pintype "passive"))
    )
    (net (code "69") (name "M3_POT") (class "Default")
      (node (ref "MOD_3") (pin "7") (pinfunction "7_7") (pintype "passive"))
      (node (ref "POTS") (pin "7") (pinfunction "CHAN2_7") (pintype "bidirectional"))
    )
    (net (code "70") (name "M3_X") (class "Default")
      (node (ref "MOD_3") (pin "6") (pinfunction "6_6") (pintype "passive"))
      (node (ref "X") (pin "7") (pinfunction "CHAN2_7") (pintype "bidirectional"))
    )
    (net (code "71") (name "M3_Y") (class "Default")
      (node (ref "MOD_3") (pin "5") (pinfunction "5_5") (pintype "passive"))
      (node (ref "Y") (pin "7") (pinfunction "CHAN2_7") (pintype "bidirectional"))
    )
    (net (code "72") (name "M4_BTN") (class "Default")
      (node (ref "BUTTONS") (pin "6") (pinfunction "CHAN3_6") (pintype "bidirectional"))
      (node (ref "MOD_4") (pin "4") (pinfunction "4_4") (pintype "passive"))
    )
    (net (code "73") (name "M4_LED1") (class "Default")
      (node (ref "MOD_4") (pin "2") (pinfunction "2_2") (pintype "passive"))
      (node (ref "R17") (pin "1") (pinfunction "1_1") (pintype "passive"))
    )
    (net (code "74") (name "M4_LED2") (class "Default")
      (node (ref "MOD_4") (pin "3") (pinfunction "3_3") (pintype "passive"))
      (node (ref "R43") (pin "1") (pinfunction "1_1") (pintype "passive"))
    )
    (net (code "75") (name "M4_POT") (class "Default")
      (node (ref "MOD_4") (pin "7") (pinfunction "7_7") (pintype "passive"))
      (node (ref "POTS") (pin "6") (pinfunction "CHAN3_6") (pintype "bidirectional"))
    )
    (net (code "76") (name "M4_X") (class "Default")
      (node (ref "MOD_4") (pin "6") (pinfunction "6_6") (pintype "passive"))
      (node (ref "X") (pin "6") (pinfunction "CHAN3_6") (pintype "bidirectional"))
    )
    (net (code "77") (name "M4_Y") (class "Default")
      (node (ref "MOD_4") (pin "5") (pinfunction "5_5") (pintype "passive"))
      (node (ref "Y") (pin "6") (pinfunction "CHAN3_6") (pintype "bidirectional"))
    )
    (net (code "78") (name "M5_BTN") (class "Default")
      (node (ref "BUTTONS") (pin "5") (pinfunction "CHAN4_5") (pintype "bidirectional"))
      (node (ref "MOD_5") (pin "4") (pinfunction "4_4") (pintype "passive"))
    )
    (net (code "79") (name "M5_LED1") (class "Default")
      (node (ref "MOD_5") (pin "2") (pinfunction "2_2") (pintype "passive"))
      (node (ref "R16") (pin "1") (pinfunction "1_1") (pintype "passive"))
    )
    (net (code "80") (name "M5_LED2") (class "Default")
      (node (ref "MOD_5") (pin "3") (pinfunction "3_3") (pintype "passive"))
      (node (ref "R42") (pin "1") (pinfunction "1_1") (pintype "passive"))
    )
    (net (code "81") (name "M5_POT") (class "Default")
      (node (ref "MOD_5") (pin "7") (pinfunction "7_7") (pintype "passive"))
      (node (ref "POTS") (pin "5") (pinfunction "CHAN4_5") (pintype "bidirectional"))
    )
    (net (code "82") (name "M5_X") (class "Default")
      (node (ref "MOD_5") (pin "6") (pinfunction "6_6") (pintype "passive"))
      (node (ref "X") (pin "5") (pinfunction "CHAN4_5") (pintype "bidirectional"))
    )
    (net (code "83") (name "M5_Y") (class "Default")
      (node (ref "MOD_5") (pin "5") (pinfunction "5_5") (pintype "passive"))
      (node (ref "Y") (pin "5") (pinfunction "CHAN4_5") (pintype "bidirectional"))
    )
    (net (code "84") (name "M6_BTN") (class "Default")
      (node (ref "BUTTONS") (pin "4") (pinfunction "CHAN5_4") (pintype "bidirectional"))
      (node (ref "MOD_6") (pin "4") (pinfunction "4_4") (pintype "passive"))
    )
    (net (code "85") (name "M6_LED1") (class "Default")
      (node (ref "MOD_6") (pin "2") (pinfunction "2_2") (pintype "passive"))
      (node (ref "R15") (pin "1") (pinfunction "1_1") (pintype "passive"))
    )
    (net (code "86") (name "M6_LED2") (class "Default")
      (node (ref "MOD_6") (pin "3") (pinfunction "3_3") (pintype "passive"))
      (node (ref "R41") (pin "1") (pinfunction "1_1") (pintype "passive"))
    )
    (net (code "87") (name "M6_POT") (class "Default")
      (node (ref "MOD_6") (pin "7") (pinfunction "7_7") (pintype "passive"))
      (node (ref "POTS") (pin "4") (pinfunction "CHAN5_4") (pintype "bidirectional"))
    )
    (net (code "88") (name "M6_X") (class "Default")
      (node (ref "MOD_6") (pin "6") (pinfunction "6_6") (pintype "passive"))
      (node (ref "X") (pin "4") (pinfunction "CHAN5_4") (pintype "bidirectional"))
    )
    (net (code "89") (name "M6_Y") (class "Default")
      (node (ref "MOD_6") (pin "5") (pinfunction "5_5") (pintype "passive"))
      (node (ref "Y") (pin "4") (pinfunction "CHAN5_4") (pintype "bidirectional"))
    )
    (net (code "90") (name "M7_BTN") (class "Default")
      (node (ref "BUTTONS") (pin "3") (pinfunction "CHAN6_3") (pintype "bidirectional"))
      (node (ref "MOD_7") (pin "4") (pinfunction "4_4") (pintype "passive"))
    )
    (net (code "91") (name "M7_LED1") (class "Default")
      (node (ref "MOD_7") (pin "2") (pinfunction "2_2") (pintype "passive"))
      (node (ref "R14") (pin "1") (pinfunction "1_1") (pintype "passive"))
    )
    (net (code "92") (name "M7_LED2") (class "Default")
      (node (ref "MOD_7") (pin "3") (pinfunction "3_3") (pintype "passive"))
      (node (ref "R40") (pin "1") (pinfunction "1_1") (pintype "passive"))
    )
    (net (code "93") (name "M7_POT") (class "Default")
      (node (ref "MOD_7") (pin "7") (pinfunction "7_7") (pintype "passive"))
      (node (ref "POTS") (pin "3") (pinfunction "CHAN6_3") (pintype "bidirectional"))
    )
    (net (code "94") (name "M7_X") (class "Default")
      (node (ref "MOD_7") (pin "6") (pinfunction "6_6") (pintype "passive"))
      (node (ref "X") (pin "3") (pinfunction "CHAN6_3") (pintype "bidirectional"))
    )
    (net (code "95") (name "M7_Y") (class "Default")
      (node (ref "MOD_7") (pin "5") (pinfunction "5_5") (pintype "passive"))
      (node (ref "Y") (pin "3") (pinfunction "CHAN6_3") (pintype "bidirectional"))
    )
    (net (code "96") (name "M8_BTN") (class "Default")
      (node (ref "BUTTONS") (pin "2") (pinfunction "CHAN7_2") (pintype "bidirectional"))
      (node (ref "MOD_8") (pin "4") (pinfunction "4_4") (pintype "passive"))
    )
    (net (code "97") (name "M8_LED1") (class "Default")
      (node (ref "MOD_8") (pin "2") (pinfunction "2_2") (pintype "passive"))
      (node (ref "R13") (pin "1") (pinfunction "1_1") (pintype "passive"))
    )
    (net (code "98") (name "M8_LED2") (class "Default")
      (node (ref "MOD_8") (pin "3") (pinfunction "3_3") (pintype "passive"))
      (node (ref "R39") (pin "1") (pinfunction "1_1") (pintype "passive"))
    )
    (net (code "99") (name "M8_POT") (class "Default")
      (node (ref "MOD_8") (pin "7") (pinfunction "7_7") (pintype "passive"))
      (node (ref "POTS") (pin "2") (pinfunction "CHAN7_2") (pintype "bidirectional"))
    )
    (net (code "100") (name "M8_X") (class "Default")
      (node (ref "MOD_8") (pin "6") (pinfunction "6_6") (pintype "passive"))
      (node (ref "X") (pin "2") (pinfunction "CHAN7_2") (pintype "bidirectional"))
    )
    (net (code "101") (name "M8_Y") (class "Default")
      (node (ref "MOD_8") (pin "5") (pinfunction "5_5") (pintype "passive"))
      (node (ref "Y") (pin "2") (pinfunction "CHAN7_2") (pintype "bidirectional"))
    )
    (net (code "102") (name "M9_BTN") (class "Default")
      (node (ref "BUTTONS") (pin "23") (pinfunction "CHAN8_23") (pintype "bidirectional"))
      (node (ref "MOD_9") (pin "4") (pinfunction "4_4") (pintype "passive"))
    )
    (net (code "103") (name "M9_LED1") (class "Default")
      (node (ref "MOD_9") (pin "2") (pinfunction "2_2") (pintype "passive"))
      (node (ref "R28") (pin "1") (pinfunction "1_1") (pintype "passive"))
    )
    (net (code "104") (name "M9_LED2") (class "Default")
      (node (ref "MOD_9") (pin "3") (pinfunction "3_3") (pintype "passive"))
      (node (ref "R54") (pin "1") (pinfunction "1_1") (pintype "passive"))
    )
    (net (code "105") (name "M9_POT") (class "Default")
      (node (ref "MOD_9") (pin "7") (pinfunction "7_7") (pintype "passive"))
      (node (ref "POTS") (pin "23") (pinfunction "CHAN8_23") (pintype "bidirectional"))
    )
    (net (code "106") (name "M9_X") (class "Default")
      (node (ref "MOD_9") (pin "6") (pinfunction "6_6") (pintype "passive"))
      (node (ref "X") (pin "23") (pinfunction "CHAN8_23") (pintype "bidirectional"))
    )
    (net (code "107") (name "M9_Y") (class "Default")
      (node (ref "MOD_9") (pin "5") (pinfunction "5_5") (pintype "passive"))
      (node (ref "Y") (pin "23") (pinfunction "CHAN8_23") (pintype "bidirectional"))
    )
    (net (code "108") (name "M10_BTN") (class "Default")
      (node (ref "BUTTONS") (pin "22") (pinfunction "CHAN9_22") (pintype "bidirectional"))
      (node (ref "MOD_10") (pin "4") (pinfunction "4_4") (pintype "passive"))
    )
    (net (code "109") (name "M10_LED1") (class "Default")
      (node (ref "MOD_10") (pin "2") (pinfunction "2_2") (pintype "passive"))
      (node (ref "R27") (pin "1") (pinfunction "1_1") (pintype "passive"))
    )
    (net (code "110") (name "M10_LED2") (class "Default")
      (node (ref "MOD_10") (pin "3") (pinfunction "3_3") (pintype "passive"))
      (node (ref "R53") (pin "1") (pinfunction "1_1") (pintype "passive"))
    )
    (net (code "111") (name "M10_POT") (class "Default")
      (node (ref "MOD_10") (pin "7") (pinfunction "7_7") (pintype "passive"))
      (node (ref "POTS") (pin "22") (pinfunction "CHAN9_22") (pintype "bidirectional"))
    )
    (net (code "112") (name "M10_X") (class "Default")
      (node (ref "MOD_10") (pin "6") (pinfunction "6_6") (pintype "passive"))
      (node (ref "X") (pin "22") (pinfunction "CHAN9_22") (pintype "bidirectional"))
    )
    (net (code "113") (name "M10_Y") (class "Default")
      (node (ref "MOD_10") (pin "5") (pinfunction "5_5") (pintype "passive"))
      (node (ref "Y") (pin "22") (pinfunction "CHAN9_22") (pintype "bidirectional"))
    )
    (net (code "114") (name "M11_BTN") (class "Default")
      (node (ref "BUTTONS") (pin "21") (pinfunction "CHAN10_21") (pintype "bidirectional"))
      (node (ref "MOD_11") (pin "4") (pinfunction "4_4") (pintype "passive"))
    )
    (net (code "115") (name "M11_LED1") (class "Default")
      (node (ref "MOD_11") (pin "2") (pinfunction "2_2") (pintype "passive"))
      (node (ref "R26") (pin "1") (pinfunction "1_1") (pintype "passive"))
    )
    (net (code "116") (name "M11_LED2") (class "Default")
      (node (ref "MOD_11") (pin "3") (pinfunction "3_3") (pintype "passive"))
      (node (ref "R52") (pin "1") (pinfunction "1_1") (pintype "passive"))
    )
    (net (code "117") (name "M11_POT") (class "Default")
      (node (ref "MOD_11") (pin "7") (pinfunction "7_7") (pintype "passive"))
      (node (ref "POTS") (pin "21") (pinfunction "CHAN10_21") (pintype "bidirectional"))
    )
    (net (code "118") (name "M11_X") (class "Default")
      (node (ref "MOD_11") (pin "6") (pinfunction "6_6") (pintype "passive"))
      (node (ref "X") (pin "21") (pinfunction "CHAN10_21") (pintype "bidirectional"))
    )
    (net (code "119") (name "M11_Y") (class "Default")
      (node (ref "MOD_11") (pin "5") (pinfunction "5_5") (pintype "passive"))
      (node (ref "Y") (pin "21") (pinfunction "CHAN10_21") (pintype "bidirectional"))
    )
    (net (code "120") (name "M12_BTN") (class "Default")
      (node (ref "BUTTONS") (pin "20") (pinfunction "CHAN11_20") (pintype "bidirectional"))
      (node (ref "MOD_12") (pin "4") (pinfunction "4_4") (pintype "passive"))
    )
    (net (code "121") (name "M12_LED1") (class "Default")
      (node (ref "MOD_12") (pin "2") (pinfunction "2_2") (pintype "passive"))
      (node (ref "R25") (pin "1") (pinfunction "1_1") (pintype "passive"))
    )
    (net (code "122") (name "M12_LED2") (class "Default")
      (node (ref "MOD_12") (pin "3") (pinfunction "3_3") (pintype "passive"))
      (node (ref "R51") (pin "1") (pinfunction "1_1") (pintype "passive"))
    )
    (net (code "123") (name "M12_POT") (class "Default")
      (node (ref "MOD_12") (pin "7") (pinfunction "7_7") (pintype "passive"))
      (node (ref "POTS") (pin "20") (pinfunction "CHAN11_20") (pintype "bidirectional"))
    )
    (net (code "124") (name "M12_X") (class "Default")
      (node (ref "MOD_12") (pin "6") (pinfunction "6_6") (pintype "passive"))
      (node (ref "X") (pin "20") (pinfunction "CHAN11_20") (pintype "bidirectional"))
    )
    (net (code "125") (name "M12_Y") (class "Default")
      (node (ref "MOD_12") (pin "5") (pinfunction "5_5") (pintype "passive"))
      (node (ref "Y") (pin "20") (pinfunction "CHAN11_20") (pintype "bidirectional"))
    )
    (net (code "126") (name "M13_BTN") (class "Default")
      (node (ref "BUTTONS") (pin "19") (pinfunction "CHAN12_19") (pintype "bidirectional"))
      (node (ref "MOD_13") (pin "4") (pinfunction "4_4") (pintype "passive"))
    )
    (net (code "127") (name "M13_LED1") (class "Default")
      (node (ref "MOD_13") (pin "2") (pinfunction "2_2") (pintype "passive"))
      (node (ref "R24") (pin "1") (pinfunction "1_1") (pintype "passive"))
    )
    (net (code "128") (name "M13_LED2") (class "Default")
      (node (ref "MOD_13") (pin "3") (pinfunction "3_3") (pintype "passive"))
      (node (ref "R50") (pin "1") (pinfunction "1_1") (pintype "passive"))
    )
    (net (code "129") (name "M13_POT") (class "Default")
      (node (ref "MOD_13") (pin "7") (pinfunction "7_7") (pintype "passive"))
      (node (ref "POTS") (pin "19") (pinfunction "CHAN12_19") (pintype "bidirectional"))
    )
    (net (code "130") (name "M13_X") (class "Default")
      (node (ref "MOD_13") (pin "6") (pinfunction "6_6") (pintype "passive"))
      (node (ref "X") (pin "19") (pinfunction "CHAN12_19") (pintype "bidirectional"))
    )
    (net (code "131") (name "M13_Y") (class "Default")
      (node (ref "MOD_13") (pin "5") (pinfunction "5_5") (pintype "passive"))
      (node (ref "Y") (pin "19") (pinfunction "CHAN12_19") (pintype "bidirectional"))
    )
    (net (code "132") (name "M14_BTN") (class "Default")
      (node (ref "BUTTONS") (pin "18") (pinfunction "CHAN13_18") (pintype "bidirectional"))
      (node (ref "MOD_14") (pin "4") (pinfunction "4_4") (pintype "passive"))
    )
    (net (code "133") (name "M14_LED1") (class "Default")
      (node (ref "MOD_14") (pin "2") (pinfunction "2_2") (pintype "passive"))
      (node (ref "R23") (pin "1") (pinfunction "1_1") (pintype "passive"))
    )
    (net (code "134") (name "M14_LED2") (class "Default")
      (node (ref "MOD_14") (pin "3") (pinfunction "3_3") (pintype "passive"))
      (node (ref "R49") (pin "1") (pinfunction "1_1") (pintype "passive"))
    )
    (net (code "135") (name "M14_POT") (class "Default")
      (node (ref "MOD_14") (pin "7") (pinfunction "7_7") (pintype "passive"))
      (node (ref "POTS") (pin "18") (pinfunction "CHAN13_18") (pintype "bidirectional"))
    )
    (net (code "136") (name "M14_X") (class "Default")
      (node (ref "MOD_14") (pin "6") (pinfunction "6_6") (pintype "passive"))
      (node (ref "X") (pin "18") (pinfunction "CHAN13_18") (pintype "bidirectional"))
    )
    (net (code "137") (name "M14_Y") (class "Default")
      (node (ref "MOD_14") (pin "5") (pinfunction "5_5") (pintype "passive"))
      (node (ref "Y") (pin "18") (pinfunction "CHAN13_18") (pintype "bidirectional"))
    )
    (net (code "138") (name "M15_BTN") (class "Default")
      (node (ref "BUTTONS") (pin "17") (pinfunction "CHAN14_17") (pintype "bidirectional"))
      (node (ref "MOD_15") (pin "4") (pinfunction "4_4") (pintype "passive"))
    )
    (net (code "139") (name "M15_LED1") (class "Default")
      (node (ref "MOD_15") (pin "2") (pinfunction "2_2") (pintype "passive"))
      (node (ref "R22") (pin "1") (pinfunction "1_1") (pintype "passive"))
    )
    (net (code "140") (name "M15_LED2") (class "Default")
      (node (ref "MOD_15") (pin "3") (pinfunction "3_3") (pintype "passive"))
      (node (ref "R48") (pin "1") (pinfunction "1_1") (pintype "passive"))
    )
    (net (code "141") (name "M15_POT") (class "Default")
      (node (ref "MOD_15") (pin "7") (pinfunction "7_7") (pintype "passive"))
      (node (ref "POTS") (pin "17") (pinfunction "CHAN14_17") (pintype "bidirectional"))
    )
    (net (code "142") (name "M15_X") (class "Default")
      (node (ref "MOD_15") (pin "6") (pinfunction "6_6") (pintype "passive"))
      (node (ref "X") (pin "17") (pinfunction "CHAN14_17") (pintype "bidirectional"))
    )
    (net (code "143") (name "M15_Y") (class "Default")
      (node (ref "MOD_15") (pin "5") (pinfunction "5_5") (pintype "passive"))
      (node (ref "Y") (pin "17") (pinfunction "CHAN14_17") (pintype "bidirectional"))
    )
    (net (code "144") (name "M16_BTN") (class "Default")
      (node (ref "BUTTONS") (pin "16") (pinfunction "CHAN15_16") (pintype "bidirectional"))
      (node (ref "MOD_16") (pin "4") (pinfunction "4_4") (pintype "passive"))
    )
    (net (code "145") (name "M16_LED1") (class "Default")
      (node (ref "MOD_16") (pin "2") (pinfunction "2_2") (pintype "passive"))
      (node (ref "R21") (pin "1") (pinfunction "1_1") (pintype "passive"))
    )
    (net (code "146") (name "M16_LED2") (class "Default")
      (node (ref "MOD_16") (pin "3") (pinfunction "3_3") (pintype "passive"))
      (node (ref "R47") (pin "1") (pinfunction "1_1") (pintype "passive"))
    )
    (net (code "147") (name "M16_POT") (class "Default")
      (node (ref "MOD_16") (pin "7") (pinfunction "7_7") (pintype "passive"))
      (node (ref "POTS") (pin "16") (pinfunction "CHAN15_16") (pintype "bidirectional"))
    )
    (net (code "148") (name "M16_X") (class "Default")
      (node (ref "MOD_16") (pin "6") (pinfunction "6_6") (pintype "passive"))
      (node (ref "X") (pin "16") (pinfunction "CHAN15_16") (pintype "bidirectional"))
    )
    (net (code "149") (name "M16_Y") (class "Default")
      (node (ref "MOD_16") (pin "5") (pinfunction "5_5") (pintype "passive"))
      (node (ref "Y") (pin "16") (pinfunction "CHAN15_16") (pintype "bidirectional"))
    )
    (net (code "150") (name "MUX1_S0") (class "Default")
      (node (ref "POTS") (pin "10") (pinfunction "S0_10") (pintype "input"))
      (node (ref "TEENSY++") (pin "D7") (pinfunction "7_D7") (pintype "bidirectional"))
    )
    (net (code "151") (name "MUX1_S1") (class "Default")
      (node (ref "POTS") (pin "11") (pinfunction "S1_11") (pintype "input"))
      (node (ref "TEENSY++") (pin "D6") (pinfunction "6,LED_D6") (pintype "bidirectional"))
    )
    (net (code "152") (name "MUX1_S2") (class "Default")
      (node (ref "POTS") (pin "14") (pinfunction "S2_14") (pintype "input"))
      (node (ref "TEENSY++") (pin "D5") (pinfunction "5_D5") (pintype "bidirectional"))
    )
    (net (code "153") (name "MUX1_S3") (class "Default")
      (node (ref "POTS") (pin "13") (pinfunction "S3_13") (pintype "input"))
      (node (ref "TEENSY++") (pin "D4") (pinfunction "4_D4") (pintype "bidirectional"))
    )
    (net (code "154") (name "MUX1_SIG") (class "Default")
      (node (ref "POTS") (pin "1") (pinfunction "COM_1") (pintype "bidirectional"))
      (node (ref "TEENSY++") (pin "F1") (pinfunction "39,A1_F1") (pintype "bidirectional"))
    )
    (net (code "155") (name "MUX2_S0") (class "Default")
      (node (ref "TEENSY++") (pin "C1") (pinfunction "11_C1") (pintype "bidirectional"))
      (node (ref "X") (pin "10") (pinfunction "S0_10") (pintype "input"))
    )
    (net (code "156") (name "MUX2_S1") (class "Default")
      (node (ref "TEENSY++") (pin "C0") (pinfunction "10_C0") (pintype "bidirectional"))
      (node (ref "X") (pin "11") (pinfunction "S1_11") (pintype "input"))
    )
    (net (code "157") (name "MUX2_S2") (class "Default")
      (node (ref "TEENSY++") (pin "E1") (pinfunction "9_E1") (pintype "bidirectional"))
      (node (ref "X") (pin "14") (pinfunction "S2_14") (pintype "input"))
    )
    (net (code "158") (name "MUX2_S3") (class "Default")
      (node (ref "TEENSY++") (pin "E0") (pinfunction "8_E0") (pintype "bidirectional"))
      (node (ref "X") (pin "13") (pinfunction "S3_13") (pintype "input"))
    )
    (net (code "159") (name "MUX2_SIG") (class "Default")
      (node (ref "TEENSY++") (pin "F2") (pinfunction "40,A2_F2") (pintype "bidirectional"))
      (node (ref "X") (pin "1") (pinfunction "COM_1") (pintype "bidirectional"))
    )
    (net (code "160") (name "MUX3_S0") (class "Default")
      (node (ref "TEENSY++") (pin "C5") (pinfunction "15,PWM_C5") (pintype "bidirectional"))
      (node (ref "Y") (pin "10") (pinfunction "S0_10") (pintype "input"))
    )
    (net (code "161") (name "MUX3_S1") (class "Default")
      (node (ref "TEENSY++") (pin "C4") (pinfunction "14,PWM_C4") (pintype "bidirectional"))
      (node (ref "Y") (pin "11") (pinfunction "S1_11") (pintype "input"))
    )
    (net (code "162") (name "MUX3_S2") (class "Default")
      (node (ref "TEENSY++") (pin "C3") (pinfunction "13_C3") (pintype "bidirectional"))
      (node (ref "Y") (pin "14") (pinfunction "S2_14") (pintype "input"))
    )
    (net (code "163") (name "MUX3_S3") (class "Default")
      (node (ref "TEENSY++") (pin "C2") (pinfunction "12_C2") (pintype "bidirectional"))
      (node (ref "Y") (pin "13") (pinfunction "S3_13") (pintype "input"))
    )
    (net (code "164") (name "MUX3_SIG") (class "Default")
      (node (ref "TEENSY++") (pin "F3") (pinfunction "41,A3_F3") (pintype "bidirectional"))
      (node (ref "Y") (pin "1") (pinfunction "COM_1") (pintype "bidirectional"))
    )
    (net (code "165") (name "MUX4_S0") (class "Default")
      (node (ref "BUTTONS") (pin "10") (pinfunction "S0_10") (pintype "input"))
      (node (ref "TEENSY++") (pin "B3") (pinfunction "23_B3") (pintype "bidirectional"))
    )
    (net (code "166") (name "MUX4_S1") (class "Default")
      (node (ref "BUTTONS") (pin "11") (pinfunction "S1_11") (pintype "input"))
      (node (ref "TEENSY++") (pin "B2") (pinfunction "22_B2") (pintype "bidirectional"))
    )
    (net (code "167") (name "MUX4_S2") (class "Default")
      (node (ref "BUTTONS") (pin "14") (pinfunction "S2_14") (pintype "input"))
      (node (ref "TEENSY++") (pin "B1") (pinfunction "21_B1") (pintype "bidirectional"))
    )
    (net (code "168") (name "MUX4_S3") (class "Default")
      (node (ref "BUTTONS") (pin "13") (pinfunction "S3_13") (pintype "input"))
      (node (ref "TEENSY++") (pin "B0") (pinfunction "20_B0") (pintype "bidirectional"))
    )
    (net (code "169") (name "MUX4_SIG") (class "Default")
      (node (ref "BUTTONS") (pin "1") (pinfunction "COM_1") (pintype "bidirectional"))
      (node (ref "TEENSY++") (pin "F4") (pinfunction "42,A4_F4") (pintype "bidirectional"))
    )
    (net (code "170") (name "Net-(LED1-PadC)") (class "Default")
      (node (ref "LED1") (pin "C") (pinfunction "C_C") (pintype "passive"))
      (node (ref "R12") (pin "1") (pinfunction "1_1") (pintype "passive"))
    )
    (net (code "171") (name "Net-(Q1-D)") (class "Default")
      (node (ref "J1") (pin "1") (pinfunction "1_1") (pintype "passive"))
      (node (ref "Q1") (pin "3") (pinfunction "D_3") (pintype "passive"))
    )
    (net (code "172") (name "SCL") (class "Default")
      (node (ref "BLUE_DRIVER") (pin "26") (pinfunction "SCL_26") (pintype "bidirectional"))
      (node (ref "BLUE_DRIVER1") (pin "26") (pinfunction "SCL_26") (pintype "bidirectional"))
      (node (ref "I2C") (pin "2") (pinfunction "2_2") (pintype "passive"))
      (node (ref "R1") (pin "P$1") (pinfunction "1_P$1") (pintype "passive"))
      (node (ref "R11") (pin "1") (pinfunction "1_1") (pintype "passive"))
      (node (ref "R37") (pin "1") (pinfunction "1_1") (pintype "passive"))
      (node (ref "TEENSY++") (pin "D0") (pinfunction "0,PWM,INT0_D0") (pintype "bidirectional"))
    )
    (net (code "173") (name "SDA") (class "Default")
      (node (ref "BLUE_DRIVER") (pin "27") (pinfunction "SDA_27") (pintype "bidirectional"))
      (node (ref "BLUE_DRIVER1") (pin "27") (pinfunction "SDA_27") (pintype "bidirectional"))
      (node (ref "I2C") (pin "1") (pinfunction "1_1") (pintype "passive"))
      (node (ref "R10") (pin "1") (pinfunction "1_1") (pintype "passive"))
      (node (ref "R2") (pin "P$2") (pinfunction "2_P$2") (pintype "passive"))
      (node (ref "R36") (pin "1") (pinfunction "1_1") (pintype "passive"))
      (node (ref "TEENSY++") (pin "D1") (pinfunction "1,PWM,INT1_D1") (pintype "bidirectional"))
    )
    (net (code "174") (name "unconnected-(TEENSY++-16,PWM-PadC6)") (class "Default")
      (node (ref "TEENSY++") (pin "C6") (pinfunction "16,PWM_C6") (pintype "bidirectional"))
    )
    (net (code "175") (name "unconnected-(TEENSY++-18,INT6-PadE6)") (class "Default")
      (node (ref "TEENSY++") (pin "E6") (pinfunction "18,INT6_E6") (pintype "bidirectional"))
    )
    (net (code "176") (name "unconnected-(TEENSY++-19-PadE7)") (class "Default")
      (node (ref "TEENSY++") (pin "E7") (pinfunction "19_E7") (pintype "bidirectional"))
    )
    (net (code "177") (name "unconnected-(TEENSY++-24,PWM-PadB4)") (class "Default")
      (node (ref "TEENSY++") (pin "B4") (pinfunction "24,PWM_B4") (pintype "bidirectional"))
    )
    (net (code "178") (name "unconnected-(TEENSY++-27,PWM-PadB7)") (class "Default")
      (node (ref "TEENSY++") (pin "B7") (pinfunction "27,PWM_B7") (pintype "bidirectional"))
    )
    (net (code "179") (name "unconnected-(TEENSY++-28-PadA0)") (class "Default")
      (node (ref "TEENSY++") (pin "A0") (pinfunction "28_A0") (pintype "bidirectional"))
    )
    (net (code "180") (name "unconnected-(TEENSY++-29-PadA1)") (class "Default")
      (node (ref "TEENSY++") (pin "A1") (pinfunction "29_A1") (pintype "bidirectional"))
    )
    (net (code "181") (name "unconnected-(TEENSY++-30-PadA2)") (class "Default")
      (node (ref "TEENSY++") (pin "A2") (pinfunction "30_A2") (pintype "bidirectional"))
    )
    (net (code "182") (name "unconnected-(TEENSY++-31-PadA3)") (class "Default")
      (node (ref "TEENSY++") (pin "A3") (pinfunction "31_A3") (pintype "bidirectional"))
    )
    (net (code "183") (name "unconnected-(TEENSY++-32-PadA4)") (class "Default")
      (node (ref "TEENSY++") (pin "A4") (pinfunction "32_A4") (pintype "bidirectional"))
    )
    (net (code "184") (name "unconnected-(TEENSY++-33-PadA5)") (class "Default")
      (node (ref "TEENSY++") (pin "A5") (pinfunction "33_A5") (pintype "bidirectional"))
    )
    (net (code "185") (name "unconnected-(TEENSY++-34-PadA6)") (class "Default")
      (node (ref "TEENSY++") (pin "A6") (pinfunction "34_A6") (pintype "bidirectional"))
    )
    (net (code "186") (name "unconnected-(TEENSY++-35-PadA7)") (class "Default")
      (node (ref "TEENSY++") (pin "A7") (pinfunction "35_A7") (pintype "bidirectional"))
    )
    (net (code "187") (name "unconnected-(TEENSY++-36,INT4-PadE4)") (class "Default")
      (node (ref "TEENSY++") (pin "E4") (pinfunction "36,INT4_E4") (pintype "bidirectional"))
    )
    (net (code "188") (name "unconnected-(TEENSY++-37,INT5-PadE5)") (class "Default")
      (node (ref "TEENSY++") (pin "E5") (pinfunction "37,INT5_E5") (pintype "bidirectional"))
    )
    (net (code "189") (name "unconnected-(TEENSY++-38,A0-PadF0)") (class "Default")
      (node (ref "TEENSY++") (pin "F0") (pinfunction "38,A0_F0") (pintype "bidirectional"))
    )
    (net (code "190") (name "unconnected-(TEENSY++-43,A5-PadF5)") (class "Default")
      (node (ref "TEENSY++") (pin "F5") (pinfunction "43,A5_F5") (pintype "bidirectional"))
    )
    (net (code "191") (name "unconnected-(TEENSY++-44,A6-PadF6)") (class "Default")
      (node (ref "TEENSY++") (pin "F6") (pinfunction "44,A6_F6") (pintype "bidirectional"))
    )
    (net (code "192") (name "unconnected-(TEENSY++-45,A7-PadF7)") (class "Default")
      (node (ref "TEENSY++") (pin "F7") (pinfunction "45,A7_F7") (pintype "bidirectional"))
    )
    (net (code "193") (name "unconnected-(TEENSY++-AREF-PadREF)") (class "Default")
      (node (ref "TEENSY++") (pin "REF") (pinfunction "AREF_REF") (pintype "input"))
    )
    (net (code "194") (name "unconnected-(TEENSY++-_RST-PadRST)") (class "Default")
      (node (ref "TEENSY++") (pin "RST") (pinfunction "_RST_RST") (pintype "input"))
    )
  )
)
